# New_rev1.net
KiCad netlist of a schematic drawn in EAGLE
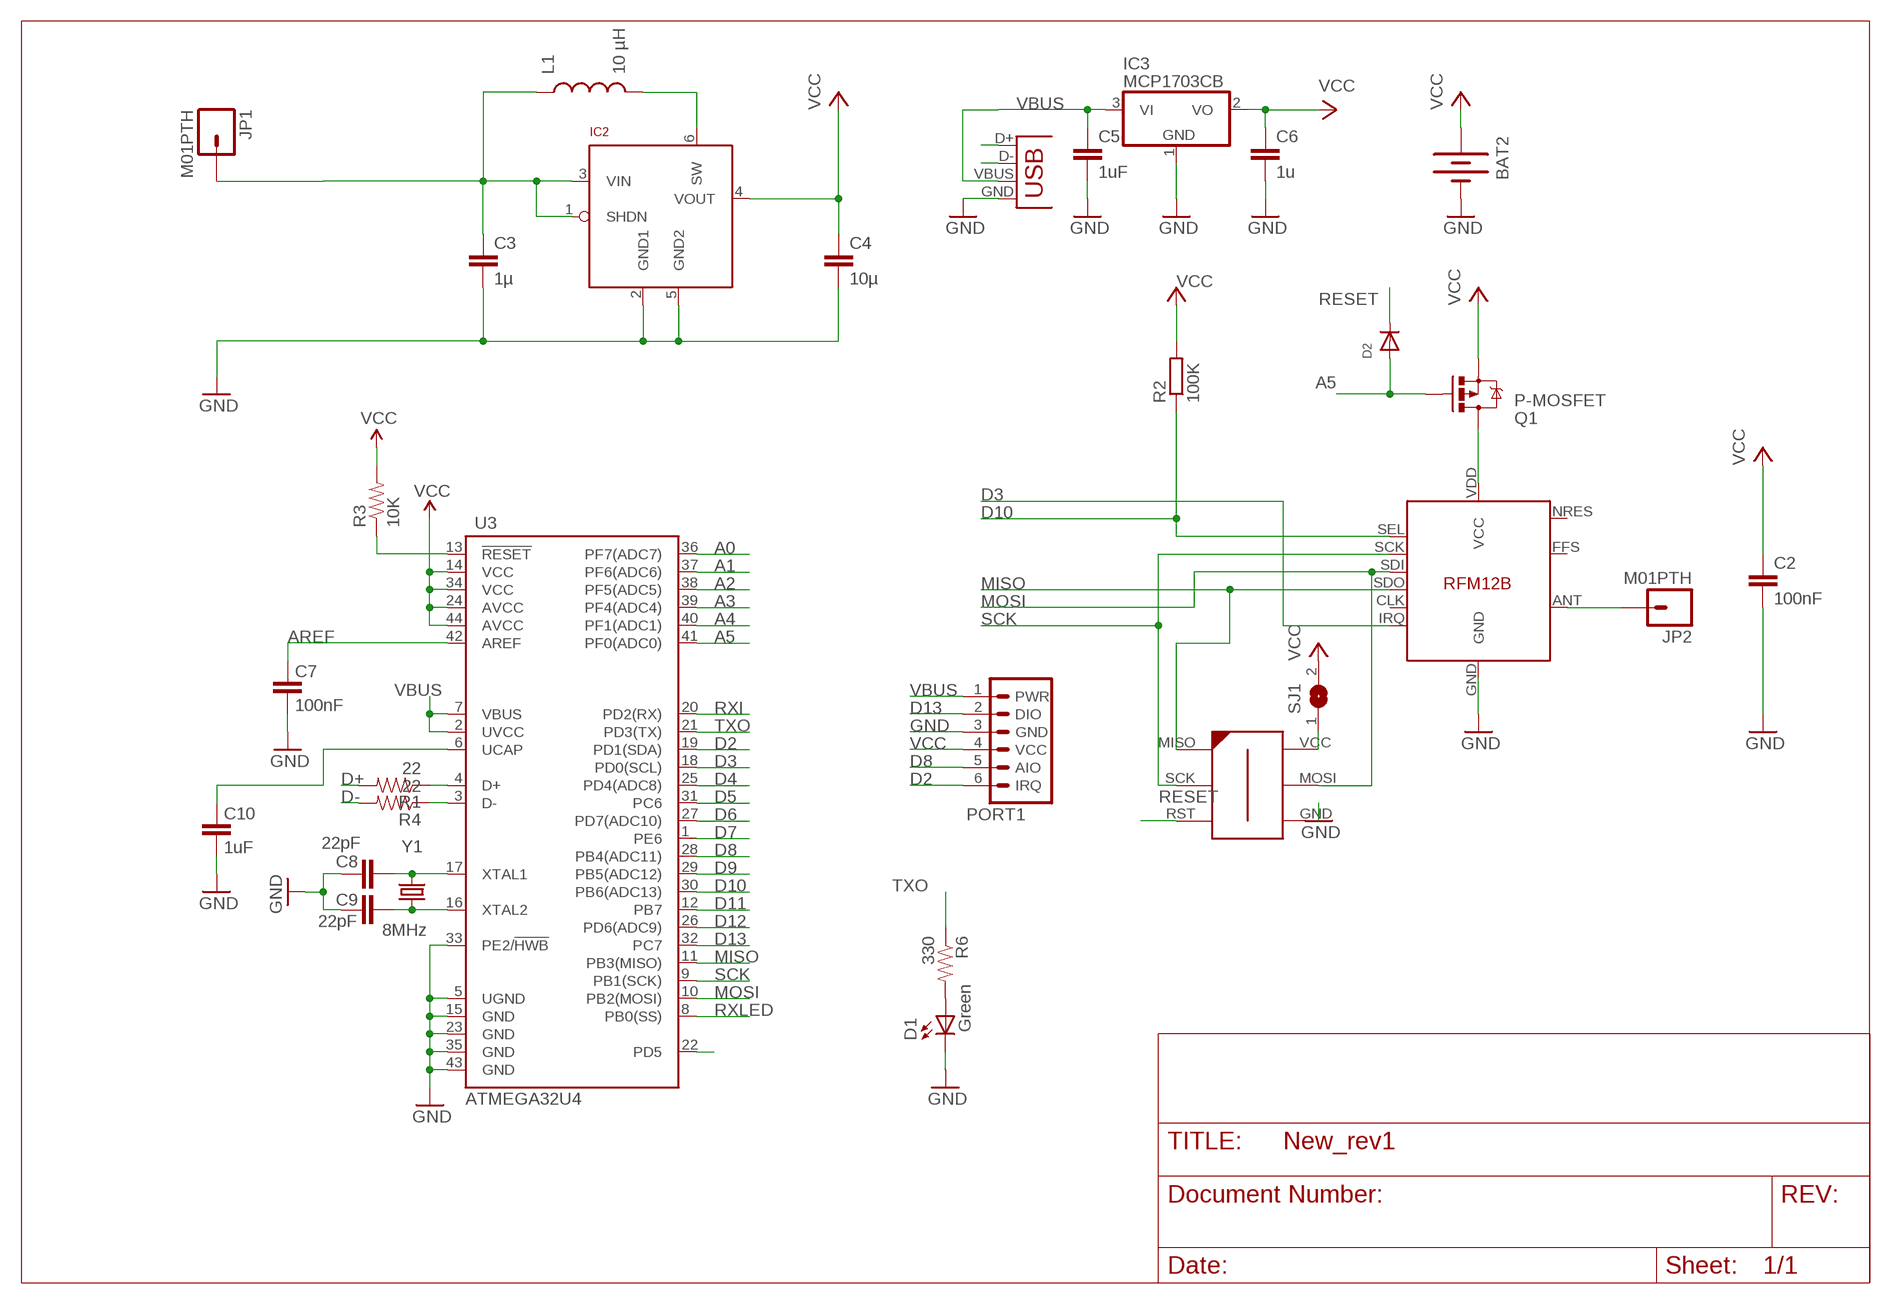
[diagram p0: schematic, sheet 1]

(export (version "E")
  (design (tool "Eeschema 10.0.6"))
  (components
    (comp (ref "BAT2")
      (value "BATTERY20PTH")
      (footprint "eagle-import:BATTCOM_20MM_PTH")
      (libsource (lib "eagle-import") (part "BATTERY20PTH"))
    )
    (comp (ref "C2")
      (value "100nF")
      (footprint "eagle-import:C0603K")
      (libsource (lib "eagle-import") (part "C-EUC0603K"))
    )
    (comp (ref "C3")
      (value "1µ")
      (footprint "eagle-import:0603-CAP")
      (libsource (lib "eagle-import") (part "CAP0603-CAP"))
    )
    (comp (ref "C4")
      (value "10µ")
      (footprint "eagle-import:0805")
      (libsource (lib "eagle-import") (part "CAP0805"))
    )
    (comp (ref "C5")
      (value "1uF")
      (footprint "eagle-import:C0603K")
      (libsource (lib "eagle-import") (part "C-EUC0603K"))
    )
    (comp (ref "C6")
      (value "1u")
      (footprint "eagle-import:C0603K")
      (libsource (lib "eagle-import") (part "C-EUC0603K"))
    )
    (comp (ref "C7")
      (value "100nF")
      (footprint "eagle-import:0402-CAP")
      (libsource (lib "eagle-import") (part "CAP0402-CAP"))
    )
    (comp (ref "C8")
      (value "22pF")
      (footprint "eagle-import:0402-CAP")
      (libsource (lib "eagle-import") (part "CAP0402-CAP"))
    )
    (comp (ref "C9")
      (value "22pF")
      (footprint "eagle-import:0402-CAP")
      (libsource (lib "eagle-import") (part "CAP0402-CAP"))
    )
    (comp (ref "C10")
      (value "1uF")
      (footprint "eagle-import:0402-CAP")
      (libsource (lib "eagle-import") (part "CAP0402-CAP"))
    )
    (comp (ref "D1")
      (value "Green")
      (footprint "eagle-import:LED-0603")
      (libsource (lib "eagle-import") (part "LED0603"))
    )
    (comp (ref "D2")
      (value "DIODESOD-323F")
      (footprint "eagle-import:SOD-323F")
      (libsource (lib "eagle-import") (part "DIODESOD-323F"))
    )
    (comp (ref "IC2")
      (value "LTC3525")
      (footprint "eagle-import:SC70")
      (libsource (lib "eagle-import") (part "LTC3525"))
    )
    (comp (ref "IC3")
      (value "MCP1703CB")
      (footprint "eagle-import:SOT23")
      (libsource (lib "eagle-import") (part "MCP1703CB"))
    )
    (comp (ref "JP1")
      (value "M01PTH")
      (footprint "eagle-import:1X01")
      (libsource (lib "eagle-import") (part "M01PTH"))
    )
    (comp (ref "JP2")
      (value "M01PTH")
      (footprint "eagle-import:1X01")
      (libsource (lib "eagle-import") (part "M01PTH"))
    )
    (comp (ref "L1")
      (value "10 µH")
      (footprint "eagle-import:1210")
      (libsource (lib "eagle-import") (part "INDUCTOR1210"))
    )
    (comp (ref "PORT1")
      (value "JEEPORT-FEMALE")
      (footprint "eagle-import:1X06_FEMALE_LOCK.010")
      (libsource (lib "eagle-import") (part "JEEPORT-FEMALE"))
    )
    (comp (ref "Q1")
      (value "P-MOSFET")
      (footprint "eagle-import:SOT23")
      (libsource (lib "eagle-import") (part "MOSFET-PCHANNEL"))
    )
    (comp (ref "R1")
      (value "22")
      (footprint "eagle-import:0402-RES")
      (libsource (lib "eagle-import") (part "RESISTOR0402-RES"))
    )
    (comp (ref "R2")
      (value "100K")
      (footprint "eagle-import:R0402")
      (libsource (lib "eagle-import") (part "R-EU_R0402"))
    )
    (comp (ref "R3")
      (value "10K")
      (footprint "eagle-import:0402-RES")
      (libsource (lib "eagle-import") (part "RESISTOR0402-RES"))
    )
    (comp (ref "R4")
      (value "22")
      (footprint "eagle-import:0402-RES")
      (libsource (lib "eagle-import") (part "RESISTOR0402-RES"))
    )
    (comp (ref "R6")
      (value "330")
      (footprint "eagle-import:0402-RES")
      (libsource (lib "eagle-import") (part "RESISTOR0402-RES"))
    )
    (comp (ref "RFM12B")
      (value "RFM12B")
      (footprint "eagle-import:RFM12B")
      (libsource (lib "eagle-import") (part "RFM12B"))
    )
    (comp (ref "SJ1") (value "SJ") (footprint "eagle-import:SJ") (libsource (lib "eagle-import") (part "SJ")))
    (comp (ref "U$2")
      (value "AVR-ISP-6-EDGE")
      (footprint "eagle-import:6PAD_ISP")
      (libsource (lib "eagle-import") (part "AVR-ISP-6-EDGE"))
    )
    (comp (ref "U3")
      (value "ATMEGA32U4")
      (footprint "eagle-import:QFN-44-NOPAD")
      (libsource (lib "eagle-import") (part "ATMEGA32U4QFN2"))
    )
    (comp (ref "X1")
      (value "USB-MICROB")
      (footprint "eagle-import:USB-MICROB")
      (libsource (lib "eagle-import") (part "USB-MICROB"))
    )
    (comp (ref "Y1")
      (value "8MHz")
      (footprint "eagle-import:CRYSTAL-SMD-5X3")
      (libsource (lib "eagle-import") (part "CRYSTAL5X3"))
    )
  )
  (nets
    (net (code "1") (name "/A0") (class "Default")
      (node (ref "U3") (pin "36") (pinfunction "PF7(ADC7)_36") (pintype "bidirectional"))
    )
    (net (code "2") (name "/A1") (class "Default")
      (node (ref "U3") (pin "37") (pinfunction "PF6(ADC6)_37") (pintype "bidirectional"))
    )
    (net (code "3") (name "/A2") (class "Default")
      (node (ref "U3") (pin "38") (pinfunction "PF5(ADC5)_38") (pintype "bidirectional"))
    )
    (net (code "4") (name "/A3") (class "Default")
      (node (ref "U3") (pin "39") (pinfunction "PF4(ADC4)_39") (pintype "bidirectional"))
    )
    (net (code "5") (name "/A4") (class "Default")
      (node (ref "U3") (pin "40") (pinfunction "PF1(ADC1)_40") (pintype "bidirectional"))
    )
    (net (code "6") (name "/A5") (class "Default")
      (node (ref "D2") (pin "A") (pinfunction "A_A") (pintype "passive"))
      (node (ref "Q1") (pin "1") (pinfunction "G_1") (pintype "passive"))
      (node (ref "U3") (pin "41") (pinfunction "PF0(ADC0)_41") (pintype "bidirectional"))
    )
    (net (code "7") (name "/AREF") (class "Default")
      (node (ref "C7") (pin "2") (pinfunction "2_2") (pintype "passive"))
      (node (ref "U3") (pin "42") (pinfunction "AREF_42") (pintype "bidirectional"))
    )
    (net (code "8") (name "/D+") (class "Default")
      (node (ref "R1") (pin "2") (pinfunction "2_2") (pintype "passive"))
      (node (ref "X1") (pin "D+") (pinfunction "D+_D+") (pintype "bidirectional"))
    )
    (net (code "9") (name "/D-") (class "Default")
      (node (ref "R4") (pin "2") (pinfunction "2_2") (pintype "passive"))
      (node (ref "X1") (pin "D-") (pinfunction "D-_D-") (pintype "bidirectional"))
    )
    (net (code "10") (name "/D2") (class "Default")
      (node (ref "PORT1") (pin "6") (pinfunction "IRQ_6") (pintype "bidirectional"))
      (node (ref "U3") (pin "19") (pinfunction "PD1(SDA)_19") (pintype "bidirectional"))
    )
    (net (code "11") (name "/D3") (class "Default")
      (node (ref "RFM12B") (pin "IRQ") (pinfunction "IRQ_IRQ") (pintype "open_collector"))
      (node (ref "U3") (pin "18") (pinfunction "PD0(SCL)_18") (pintype "bidirectional"))
    )
    (net (code "12") (name "/D4") (class "Default")
      (node (ref "U3") (pin "25") (pinfunction "PD4(ADC8)_25") (pintype "bidirectional"))
    )
    (net (code "13") (name "/D5") (class "Default")
      (node (ref "U3") (pin "31") (pinfunction "PC6_31") (pintype "bidirectional"))
    )
    (net (code "14") (name "/D6") (class "Default")
      (node (ref "U3") (pin "27") (pinfunction "PD7(ADC10)_27") (pintype "bidirectional"))
    )
    (net (code "15") (name "/D7") (class "Default")
      (node (ref "U3") (pin "1") (pinfunction "PE6_1") (pintype "bidirectional"))
    )
    (net (code "16") (name "/D8") (class "Default")
      (node (ref "PORT1") (pin "5") (pinfunction "AIO_5") (pintype "bidirectional"))
      (node (ref "U3") (pin "28") (pinfunction "PB4(ADC11)_28") (pintype "bidirectional"))
    )
    (net (code "17") (name "/D9") (class "Default")
      (node (ref "U3") (pin "29") (pinfunction "PB5(ADC12)_29") (pintype "bidirectional"))
    )
    (net (code "18") (name "/D10") (class "Default")
      (node (ref "R2") (pin "1") (pinfunction "1_1") (pintype "passive"))
      (node (ref "RFM12B") (pin "SEL") (pinfunction "SEL_SEL") (pintype "input"))
      (node (ref "U3") (pin "30") (pinfunction "PB6(ADC13)_30") (pintype "bidirectional"))
    )
    (net (code "19") (name "/D11") (class "Default")
      (node (ref "U3") (pin "12") (pinfunction "PB7_12") (pintype "bidirectional"))
    )
    (net (code "20") (name "/D12") (class "Default")
      (node (ref "U3") (pin "26") (pinfunction "PD6(ADC9)_26") (pintype "bidirectional"))
    )
    (net (code "21") (name "/D13") (class "Default")
      (node (ref "PORT1") (pin "2") (pinfunction "DIO_2") (pintype "bidirectional"))
      (node (ref "U3") (pin "32") (pinfunction "PC7_32") (pintype "bidirectional"))
    )
    (net (code "22") (name "/MISO") (class "Default")
      (node (ref "RFM12B") (pin "SDO") (pinfunction "SDO_SDO") (pintype "output"))
      (node (ref "U$2") (pin "MISO") (pinfunction "P$1_MISO") (pintype "bidirectional"))
      (node (ref "U3") (pin "11") (pinfunction "PB3(MISO)_11") (pintype "bidirectional"))
    )
    (net (code "23") (name "/MOSI") (class "Default")
      (node (ref "RFM12B") (pin "SDI") (pinfunction "SDI_SDI") (pintype "input"))
      (node (ref "U$2") (pin "MOSI") (pinfunction "P$5_MOSI") (pintype "bidirectional"))
      (node (ref "U3") (pin "10") (pinfunction "PB2(MOSI)_10") (pintype "bidirectional"))
    )
    (net (code "24") (name "/RESET") (class "Default")
      (node (ref "D2") (pin "C") (pinfunction "C_C") (pintype "passive"))
      (node (ref "R3") (pin "1") (pinfunction "1_1") (pintype "passive"))
      (node (ref "U$2") (pin "RST") (pinfunction "P$3_RST") (pintype "bidirectional"))
      (node (ref "U3") (pin "13") (pinfunction "~{RESET}_13") (pintype "bidirectional"))
    )
    (net (code "25") (name "/RXI") (class "Default")
      (node (ref "U3") (pin "20") (pinfunction "PD2(RX)_20") (pintype "bidirectional"))
    )
    (net (code "26") (name "/RXLED") (class "Default")
      (node (ref "U3") (pin "8") (pinfunction "PB0(SS)_8") (pintype "bidirectional"))
    )
    (net (code "27") (name "/SCK") (class "Default")
      (node (ref "RFM12B") (pin "SCK") (pinfunction "SCK_SCK") (pintype "input"))
      (node (ref "U$2") (pin "SCK") (pinfunction "P$2_SCK") (pintype "bidirectional"))
      (node (ref "U3") (pin "9") (pinfunction "PB1(SCK)_9") (pintype "bidirectional"))
    )
    (net (code "28") (name "/TXO") (class "Default")
      (node (ref "R6") (pin "1") (pinfunction "1_1") (pintype "passive"))
      (node (ref "U3") (pin "21") (pinfunction "PD3(TX)_21") (pintype "bidirectional"))
    )
    (net (code "29") (name "/VBUS") (class "Default")
      (node (ref "C5") (pin "1") (pinfunction "1_1") (pintype "passive"))
      (node (ref "IC3") (pin "3") (pinfunction "VI_3") (pintype "input"))
      (node (ref "PORT1") (pin "1") (pinfunction "PWR_1") (pintype "power_in"))
      (node (ref "U3") (pin "2") (pinfunction "UVCC_2") (pintype "bidirectional"))
      (node (ref "U3") (pin "7") (pinfunction "VBUS_7") (pintype "bidirectional"))
      (node (ref "X1") (pin "VBUS") (pinfunction "VBUS_VBUS") (pintype "bidirectional"))
    )
    (net (code "30") (name "GND") (class "Default")
      (node (ref "BAT2") (pin "2") (pinfunction "-_2") (pintype "power_in"))
      (node (ref "C10") (pin "1") (pinfunction "1_1") (pintype "passive"))
      (node (ref "C2") (pin "2") (pinfunction "2_2") (pintype "passive"))
      (node (ref "C3") (pin "2") (pinfunction "2_2") (pintype "passive"))
      (node (ref "C4") (pin "2") (pinfunction "2_2") (pintype "passive"))
      (node (ref "C5") (pin "2") (pinfunction "2_2") (pintype "passive"))
      (node (ref "C6") (pin "2") (pinfunction "2_2") (pintype "passive"))
      (node (ref "C7") (pin "1") (pinfunction "1_1") (pintype "passive"))
      (node (ref "C8") (pin "2") (pinfunction "2_2") (pintype "passive"))
      (node (ref "C9") (pin "2") (pinfunction "2_2") (pintype "passive"))
      (node (ref "D1") (pin "C") (pinfunction "C_C") (pintype "passive"))
      (node (ref "IC2") (pin "2") (pinfunction "GND1_2") (pintype "power_in"))
      (node (ref "IC2") (pin "5") (pinfunction "GND2_5") (pintype "power_in"))
      (node (ref "IC3") (pin "1") (pinfunction "GND_1") (pintype "passive"))
      (node (ref "PORT1") (pin "3") (pinfunction "GND_3") (pintype "power_in"))
      (node (ref "RFM12B") (pin "GND") (pinfunction "GND_GND") (pintype "power_in"))
      (node (ref "U$2") (pin "GND") (pinfunction "P$4_GND") (pintype "bidirectional"))
      (node (ref "U3") (pin "15") (pinfunction "GND_15") (pintype "bidirectional"))
      (node (ref "U3") (pin "23") (pinfunction "GND_23") (pintype "bidirectional"))
      (node (ref "U3") (pin "33") (pinfunction "PE2/~{HWB}_33") (pintype "bidirectional"))
      (node (ref "U3") (pin "35") (pinfunction "GND_35") (pintype "bidirectional"))
      (node (ref "U3") (pin "43") (pinfunction "GND_43") (pintype "bidirectional"))
      (node (ref "U3") (pin "5") (pinfunction "UGND_5") (pintype "bidirectional"))
      (node (ref "X1") (pin "GND") (pinfunction "GND_GND") (pintype "bidirectional"))
    )
    (net (code "31") (name "Net-(D1-PadA)") (class "Default")
      (node (ref "D1") (pin "A") (pinfunction "A_A") (pintype "passive"))
      (node (ref "R6") (pin "2") (pinfunction "2_2") (pintype "passive"))
    )
    (net (code "32") (name "Net-(IC2-SHDN)") (class "Default")
      (node (ref "C3") (pin "1") (pinfunction "1_1") (pintype "passive"))
      (node (ref "IC2") (pin "1") (pinfunction "SHDN_1") (pintype "input"))
      (node (ref "IC2") (pin "3") (pinfunction "VIN_3") (pintype "tri_state"))
      (node (ref "JP1") (pin "1") (pinfunction "1_1") (pintype "passive"))
      (node (ref "L1") (pin "1") (pinfunction "1_1") (pintype "passive"))
    )
    (net (code "33") (name "Net-(IC2-SW)") (class "Default")
      (node (ref "IC2") (pin "6") (pinfunction "SW_6") (pintype "power_in"))
      (node (ref "L1") (pin "2") (pinfunction "2_2") (pintype "passive"))
    )
    (net (code "34") (name "Net-(JP2-Pad1)") (class "Default")
      (node (ref "JP2") (pin "1") (pinfunction "1_1") (pintype "passive"))
      (node (ref "RFM12B") (pin "ANT") (pinfunction "ANT_ANT") (pintype "passive"))
    )
    (net (code "35") (name "Net-(Q1-D)") (class "Default")
      (node (ref "Q1") (pin "3") (pinfunction "D_3") (pintype "passive"))
      (node (ref "RFM12B") (pin "VDD") (pinfunction "VCC_VDD") (pintype "power_in"))
    )
    (net (code "36") (name "Net-(U$2-P$6)") (class "Default")
      (node (ref "SJ1") (pin "1") (pinfunction "1_1") (pintype "passive"))
      (node (ref "U$2") (pin "VCC") (pinfunction "P$6_VCC") (pintype "bidirectional"))
    )
    (net (code "37") (name "Net-(U3-D+)") (class "Default")
      (node (ref "R1") (pin "1") (pinfunction "1_1") (pintype "passive"))
      (node (ref "U3") (pin "4") (pinfunction "D+_4") (pintype "bidirectional"))
    )
    (net (code "38") (name "Net-(U3-D-)") (class "Default")
      (node (ref "R4") (pin "1") (pinfunction "1_1") (pintype "passive"))
      (node (ref "U3") (pin "3") (pinfunction "D-_3") (pintype "bidirectional"))
    )
    (net (code "39") (name "Net-(U3-UCAP)") (class "Default")
      (node (ref "C10") (pin "2") (pinfunction "2_2") (pintype "passive"))
      (node (ref "U3") (pin "6") (pinfunction "UCAP_6") (pintype "bidirectional"))
    )
    (net (code "40") (name "Net-(U3-XTAL1)") (class "Default")
      (node (ref "C8") (pin "1") (pinfunction "1_1") (pintype "passive"))
      (node (ref "U3") (pin "17") (pinfunction "XTAL1_17") (pintype "bidirectional"))
      (node (ref "Y1") (pin "3") (pinfunction "2_3") (pintype "passive"))
    )
    (net (code "41") (name "Net-(U3-XTAL2)") (class "Default")
      (node (ref "C9") (pin "1") (pinfunction "1_1") (pintype "passive"))
      (node (ref "U3") (pin "16") (pinfunction "XTAL2_16") (pintype "bidirectional"))
      (node (ref "Y1") (pin "1") (pinfunction "1_1") (pintype "passive"))
    )
    (net (code "42") (name "VCC") (class "Default")
      (node (ref "BAT2") (pin "1") (pinfunction "+_1") (pintype "power_in"))
      (node (ref "C2") (pin "1") (pinfunction "1_1") (pintype "passive"))
      (node (ref "C4") (pin "1") (pinfunction "1_1") (pintype "passive"))
      (node (ref "C6") (pin "1") (pinfunction "1_1") (pintype "passive"))
      (node (ref "IC2") (pin "4") (pinfunction "VOUT_4") (pintype "power_in"))
      (node (ref "IC3") (pin "2") (pinfunction "VO_2") (pintype "passive"))
      (node (ref "PORT1") (pin "4") (pinfunction "VCC_4") (pintype "power_in"))
      (node (ref "Q1") (pin "2") (pinfunction "S_2") (pintype "passive"))
      (node (ref "R2") (pin "2") (pinfunction "2_2") (pintype "passive"))
      (node (ref "R3") (pin "2") (pinfunction "2_2") (pintype "passive"))
      (node (ref "SJ1") (pin "2") (pinfunction "2_2") (pintype "passive"))
      (node (ref "U3") (pin "14") (pinfunction "VCC_14") (pintype "bidirectional"))
      (node (ref "U3") (pin "24") (pinfunction "AVCC_24") (pintype "bidirectional"))
      (node (ref "U3") (pin "34") (pinfunction "VCC_34") (pintype "bidirectional"))
      (node (ref "U3") (pin "44") (pinfunction "AVCC_44") (pintype "bidirectional"))
    )
    (net (code "43") (name "unconnected-(RFM12B-PadCLK)") (class "Default")
      (node (ref "RFM12B") (pin "CLK") (pinfunction "CLK_CLK") (pintype "output"))
    )
    (net (code "44") (name "unconnected-(RFM12B-PadFFS)") (class "Default")
      (node (ref "RFM12B") (pin "FFS") (pinfunction "FFS_FFS") (pintype "bidirectional"))
    )
    (net (code "45") (name "unconnected-(RFM12B-PadNRES)") (class "Default")
      (node (ref "RFM12B") (pin "NRES") (pinfunction "NRES_NRES") (pintype "input"))
    )
    (net (code "46") (name "unconnected-(U3-PD5-Pad22)") (class "Default")
      (node (ref "U3") (pin "22") (pinfunction "PD5_22") (pintype "bidirectional"))
    )
  )
)
